# 5V_TO_3V_VD.net
KiCad netlist of a schematic drawn in Altium Designer
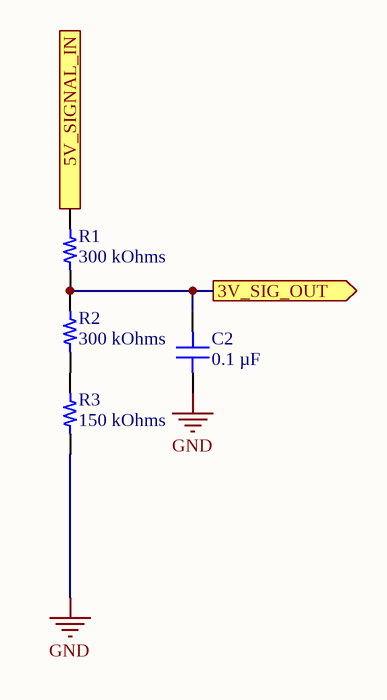
[diagram p0: 5V_TO_3V_VD.SchDoc]

(export (version "E")
  (design (tool "Eeschema 10.0.6"))
  (components
    (comp (ref "C2")
      (value "0.1 µF")
      (footprint "CAP 0805_2012")
      (description "CAP CER 0.1UF 50V X7R 0805")
      (fields (field (name "PART NUMBER") "CC0805MRX7R9BB104") (field (name "MANUFACTURER") "Yageo"))
      (libsource (lib "Celestial Altium Library - altium_library") (part "Capacitor"))
    )
    (comp (ref "R1")
      (value "300 kOhms")
      (footprint "RES 0805_2012")
      (description "RES SMD 300K OHM 5% 1/8W 0805")
      (fields (field (name "PART NUMBER") "CRCW0805300KJNEA") (field (name "MANUFACTURER") "Vishay Dale"))
      (libsource (lib "Celestial Altium Library - altium_library") (part "Resistor"))
    )
    (comp (ref "R2")
      (value "300 kOhms")
      (footprint "RES 0805_2012")
      (description "RES SMD 300K OHM 5% 1/8W 0805")
      (fields (field (name "PART NUMBER") "CRCW0805300KJNEA") (field (name "MANUFACTURER") "Vishay Dale"))
      (libsource (lib "Celestial Altium Library - altium_library") (part "Resistor"))
    )
    (comp (ref "R3")
      (value "150 kOhms")
      (footprint "RES 0805_2012")
      (description "RES SMD 150K OHM 0.5% 1/8W 0805")
      (fields (field (name "PART NUMBER") "RT0805DRD07150KL") (field (name "MANUFACTURER") "Yageo"))
      (libsource (lib "Celestial Altium Library - altium_library") (part "Resistor"))
    )
  )
  (nets
    (net (code "1") (name "/3V_SIG_OUT") (class "Default")
      (node (ref "C2") (pin "2") (pinfunction "2_2") (pintype "passive"))
      (node (ref "R1") (pin "1") (pinfunction "1_1") (pintype "passive"))
      (node (ref "R2") (pin "2") (pinfunction "2_2") (pintype "passive"))
    )
    (net (code "2") (name "/5V_SIGNAL_IN") (class "Default")
      (node (ref "R1") (pin "2") (pinfunction "2_2") (pintype "passive"))
    )
    (net (code "3") (name "GND") (class "Default")
      (node (ref "C2") (pin "1") (pinfunction "1_1") (pintype "passive"))
      (node (ref "R3") (pin "1") (pinfunction "1_1") (pintype "passive"))
    )
    (net (code "4") (name "Net-(R2-Pad1)") (class "Default")
      (node (ref "R2") (pin "1") (pinfunction "1_1") (pintype "passive"))
      (node (ref "R3") (pin "2") (pinfunction "2_2") (pintype "passive"))
    )
  )
)
